# bat_charger.net
KiCad netlist of a schematic drawn in EAGLE
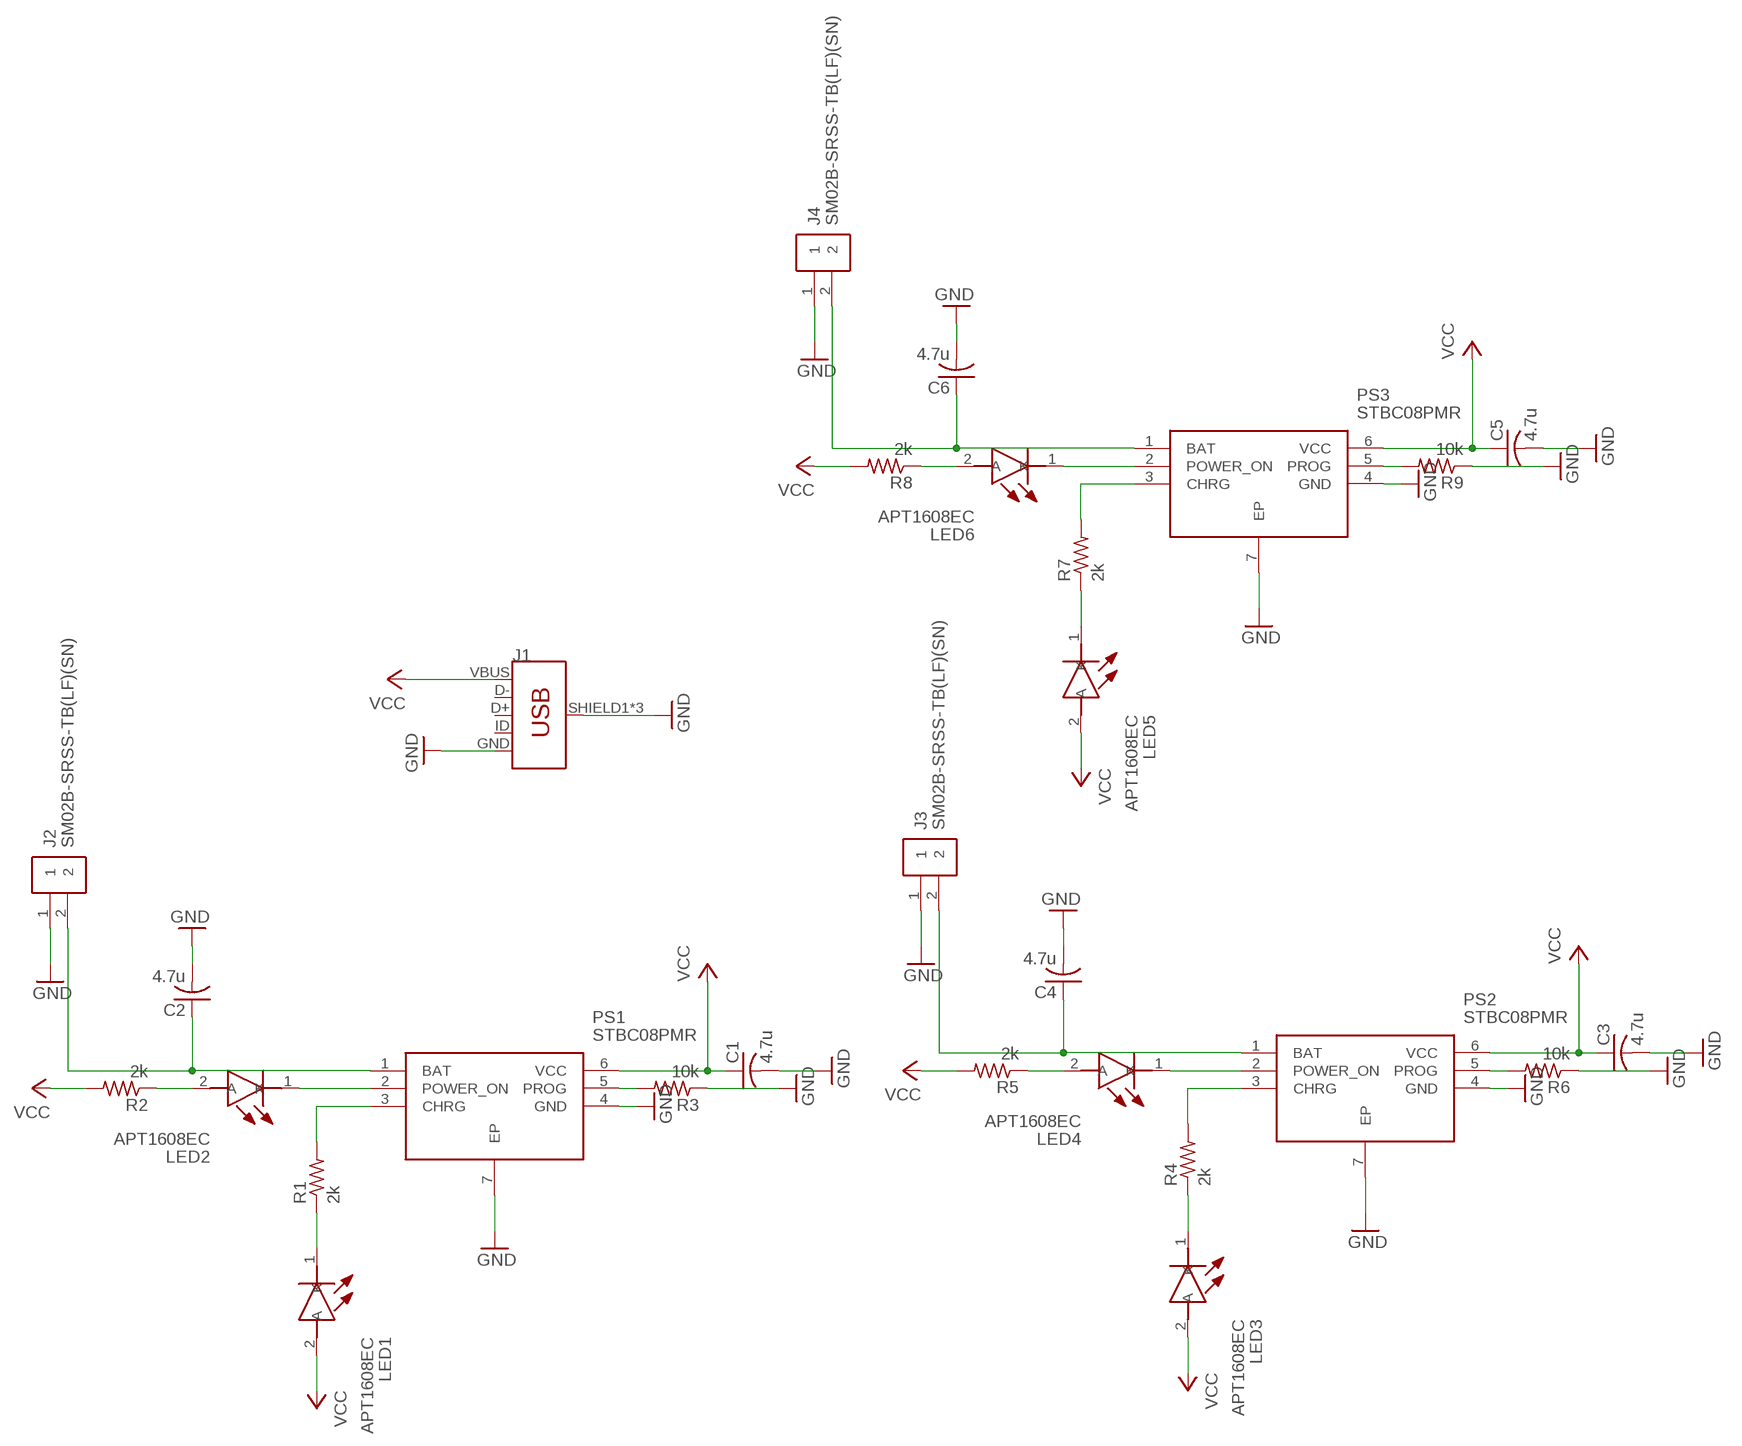
[diagram p0: schematic, sheet 1]

(export (version "E")
  (design (tool "Eeschema 10.0.6"))
  (components
    (comp (ref "C1")
      (value "4.7u")
      (footprint "eagle-import:C0603")
      (libsource (lib "eagle-import") (part "C-USC0603"))
    )
    (comp (ref "C2")
      (value "4.7u")
      (footprint "eagle-import:C0603")
      (libsource (lib "eagle-import") (part "C-USC0603"))
    )
    (comp (ref "C3")
      (value "4.7u")
      (footprint "eagle-import:C0603")
      (libsource (lib "eagle-import") (part "C-USC0603"))
    )
    (comp (ref "C4")
      (value "4.7u")
      (footprint "eagle-import:C0603")
      (libsource (lib "eagle-import") (part "C-USC0603"))
    )
    (comp (ref "C5")
      (value "4.7u")
      (footprint "eagle-import:C0603")
      (libsource (lib "eagle-import") (part "C-USC0603"))
    )
    (comp (ref "C6")
      (value "4.7u")
      (footprint "eagle-import:C0603")
      (libsource (lib "eagle-import") (part "C-USC0603"))
    )
    (comp (ref "J1")
      (value "USB_MICRO-B_FEMALE-SMT")
      (footprint "eagle-import:USB-B-MICRO-SMD")
      (libsource (lib "eagle-import") (part "USB_MICRO-B_FEMALE-SMT"))
    )
    (comp (ref "J2")
      (value "SM02B-SRSS-TB(LF)(SN)")
      (footprint "eagle-import:SM02B-SRSS-TB(LF)(SN)")
      (fields (field (name "MF") "JST Sales"))
      (libsource (lib "eagle-import") (part "SM02B-SRSS-TB(LF)(SN)"))
    )
    (comp (ref "J3")
      (value "SM02B-SRSS-TB(LF)(SN)")
      (footprint "eagle-import:SM02B-SRSS-TB(LF)(SN)")
      (fields (field (name "MF") "JST Sales"))
      (libsource (lib "eagle-import") (part "SM02B-SRSS-TB(LF)(SN)"))
    )
    (comp (ref "J4")
      (value "SM02B-SRSS-TB(LF)(SN)")
      (footprint "eagle-import:SM02B-SRSS-TB(LF)(SN)")
      (fields (field (name "MF") "JST Sales"))
      (libsource (lib "eagle-import") (part "SM02B-SRSS-TB(LF)(SN)"))
    )
    (comp (ref "LED1")
      (value "APT1608EC")
      (footprint "eagle-import:LEDC1608X85N")
      (fields (field (name "MOUSER_PART_NUMBER") "604-APT1608EC"))
      (libsource (lib "eagle-import") (part "APT1608EC"))
    )
    (comp (ref "LED2")
      (value "APT1608EC")
      (footprint "eagle-import:LEDC1608X85N")
      (fields (field (name "MOUSER_PART_NUMBER") "604-APT1608EC"))
      (libsource (lib "eagle-import") (part "APT1608EC"))
    )
    (comp (ref "LED3")
      (value "APT1608EC")
      (footprint "eagle-import:LEDC1608X85N")
      (fields (field (name "MOUSER_PART_NUMBER") "604-APT1608EC"))
      (libsource (lib "eagle-import") (part "APT1608EC"))
    )
    (comp (ref "LED4")
      (value "APT1608EC")
      (footprint "eagle-import:LEDC1608X85N")
      (fields (field (name "MOUSER_PART_NUMBER") "604-APT1608EC"))
      (libsource (lib "eagle-import") (part "APT1608EC"))
    )
    (comp (ref "LED5")
      (value "APT1608EC")
      (footprint "eagle-import:LEDC1608X85N")
      (fields (field (name "MOUSER_PART_NUMBER") "604-APT1608EC"))
      (libsource (lib "eagle-import") (part "APT1608EC"))
    )
    (comp (ref "LED6")
      (value "APT1608EC")
      (footprint "eagle-import:LEDC1608X85N")
      (fields (field (name "MOUSER_PART_NUMBER") "604-APT1608EC"))
      (libsource (lib "eagle-import") (part "APT1608EC"))
    )
    (comp (ref "PS1")
      (value "STBC08PMR")
      (footprint "eagle-import:SON95P300X300X100-7N")
      (fields (field (name "MOUSER_PART_NUMBER") "511-STBC08PMR"))
      (libsource (lib "eagle-import") (part "STBC08PMR"))
    )
    (comp (ref "PS2")
      (value "STBC08PMR")
      (footprint "eagle-import:SON95P300X300X100-7N")
      (fields (field (name "MOUSER_PART_NUMBER") "511-STBC08PMR"))
      (libsource (lib "eagle-import") (part "STBC08PMR"))
    )
    (comp (ref "PS3")
      (value "STBC08PMR")
      (footprint "eagle-import:SON95P300X300X100-7N")
      (fields (field (name "MOUSER_PART_NUMBER") "511-STBC08PMR"))
      (libsource (lib "eagle-import") (part "STBC08PMR"))
    )
    (comp (ref "R1")
      (value "2k")
      (footprint "eagle-import:R0603")
      (libsource (lib "eagle-import") (part "R-US_R0603"))
    )
    (comp (ref "R2")
      (value "2k")
      (footprint "eagle-import:R0603")
      (libsource (lib "eagle-import") (part "R-US_R0603"))
    )
    (comp (ref "R3")
      (value "10k")
      (footprint "eagle-import:R0603")
      (libsource (lib "eagle-import") (part "R-US_R0603"))
    )
    (comp (ref "R4")
      (value "2k")
      (footprint "eagle-import:R0603")
      (libsource (lib "eagle-import") (part "R-US_R0603"))
    )
    (comp (ref "R5")
      (value "2k")
      (footprint "eagle-import:R0603")
      (libsource (lib "eagle-import") (part "R-US_R0603"))
    )
    (comp (ref "R6")
      (value "10k")
      (footprint "eagle-import:R0603")
      (libsource (lib "eagle-import") (part "R-US_R0603"))
    )
    (comp (ref "R7")
      (value "2k")
      (footprint "eagle-import:R0603")
      (libsource (lib "eagle-import") (part "R-US_R0603"))
    )
    (comp (ref "R8")
      (value "2k")
      (footprint "eagle-import:R0603")
      (libsource (lib "eagle-import") (part "R-US_R0603"))
    )
    (comp (ref "R9")
      (value "10k")
      (footprint "eagle-import:R0603")
      (libsource (lib "eagle-import") (part "R-US_R0603"))
    )
  )
  (nets
    (net (code "1") (name "GND") (class "Default")
      (node (ref "C1") (pin "2") (pinfunction "2_2") (pintype "passive"))
      (node (ref "C2") (pin "2") (pinfunction "2_2") (pintype "passive"))
      (node (ref "C3") (pin "2") (pinfunction "2_2") (pintype "passive"))
      (node (ref "C4") (pin "2") (pinfunction "2_2") (pintype "passive"))
      (node (ref "C5") (pin "2") (pinfunction "2_2") (pintype "passive"))
      (node (ref "C6") (pin "2") (pinfunction "2_2") (pintype "passive"))
      (node (ref "J1") (pin "GND") (pinfunction "GND_GND") (pintype "power_in"))
      (node (ref "J1") (pin "SHIELD1") (pinfunction "SHIELD_SHIELD1") (pintype "bidirectional"))
      (node (ref "J1") (pin "SHIELD2") (pinfunction "SHIELD_SHIELD2") (pintype "bidirectional"))
      (node (ref "J1") (pin "SHIELD3") (pinfunction "SHIELD_SHIELD3") (pintype "bidirectional"))
      (node (ref "J2") (pin "1") (pinfunction "1_1") (pintype "bidirectional"))
      (node (ref "J3") (pin "1") (pinfunction "1_1") (pintype "bidirectional"))
      (node (ref "J4") (pin "1") (pinfunction "1_1") (pintype "bidirectional"))
      (node (ref "PS1") (pin "4") (pinfunction "GND_4") (pintype "power_in"))
      (node (ref "PS1") (pin "7") (pinfunction "EP_7") (pintype "power_in"))
      (node (ref "PS2") (pin "4") (pinfunction "GND_4") (pintype "power_in"))
      (node (ref "PS2") (pin "7") (pinfunction "EP_7") (pintype "power_in"))
      (node (ref "PS3") (pin "4") (pinfunction "GND_4") (pintype "power_in"))
      (node (ref "PS3") (pin "7") (pinfunction "EP_7") (pintype "power_in"))
      (node (ref "R3") (pin "1") (pinfunction "1_1") (pintype "passive"))
      (node (ref "R6") (pin "1") (pinfunction "1_1") (pintype "passive"))
      (node (ref "R9") (pin "1") (pinfunction "1_1") (pintype "passive"))
    )
    (net (code "2") (name "Net-(LED1-K)") (class "Default")
      (node (ref "LED1") (pin "1") (pinfunction "K_1") (pintype "bidirectional"))
      (node (ref "R1") (pin "1") (pinfunction "1_1") (pintype "passive"))
    )
    (net (code "3") (name "Net-(LED2-A)") (class "Default")
      (node (ref "LED2") (pin "2") (pinfunction "A_2") (pintype "bidirectional"))
      (node (ref "R2") (pin "1") (pinfunction "1_1") (pintype "passive"))
    )
    (net (code "4") (name "Net-(LED2-K)") (class "Default")
      (node (ref "LED2") (pin "1") (pinfunction "K_1") (pintype "bidirectional"))
      (node (ref "PS1") (pin "2") (pinfunction "POWER_ON_2") (pintype "bidirectional"))
    )
    (net (code "5") (name "Net-(LED3-K)") (class "Default")
      (node (ref "LED3") (pin "1") (pinfunction "K_1") (pintype "bidirectional"))
      (node (ref "R4") (pin "1") (pinfunction "1_1") (pintype "passive"))
    )
    (net (code "6") (name "Net-(LED4-A)") (class "Default")
      (node (ref "LED4") (pin "2") (pinfunction "A_2") (pintype "bidirectional"))
      (node (ref "R5") (pin "1") (pinfunction "1_1") (pintype "passive"))
    )
    (net (code "7") (name "Net-(LED4-K)") (class "Default")
      (node (ref "LED4") (pin "1") (pinfunction "K_1") (pintype "bidirectional"))
      (node (ref "PS2") (pin "2") (pinfunction "POWER_ON_2") (pintype "bidirectional"))
    )
    (net (code "8") (name "Net-(LED5-K)") (class "Default")
      (node (ref "LED5") (pin "1") (pinfunction "K_1") (pintype "bidirectional"))
      (node (ref "R7") (pin "1") (pinfunction "1_1") (pintype "passive"))
    )
    (net (code "9") (name "Net-(LED6-A)") (class "Default")
      (node (ref "LED6") (pin "2") (pinfunction "A_2") (pintype "bidirectional"))
      (node (ref "R8") (pin "1") (pinfunction "1_1") (pintype "passive"))
    )
    (net (code "10") (name "Net-(LED6-K)") (class "Default")
      (node (ref "LED6") (pin "1") (pinfunction "K_1") (pintype "bidirectional"))
      (node (ref "PS3") (pin "2") (pinfunction "POWER_ON_2") (pintype "bidirectional"))
    )
    (net (code "11") (name "Net-(PS1-BAT)") (class "Default")
      (node (ref "C2") (pin "1") (pinfunction "1_1") (pintype "passive"))
      (node (ref "J2") (pin "2") (pinfunction "2_2") (pintype "bidirectional"))
      (node (ref "PS1") (pin "1") (pinfunction "BAT_1") (pintype "output"))
    )
    (net (code "12") (name "Net-(PS1-CHRG)") (class "Default")
      (node (ref "PS1") (pin "3") (pinfunction "CHRG_3") (pintype "output"))
      (node (ref "R1") (pin "2") (pinfunction "2_2") (pintype "passive"))
    )
    (net (code "13") (name "Net-(PS1-PROG)") (class "Default")
      (node (ref "PS1") (pin "5") (pinfunction "PROG_5") (pintype "input"))
      (node (ref "R3") (pin "2") (pinfunction "2_2") (pintype "passive"))
    )
    (net (code "14") (name "Net-(PS2-BAT)") (class "Default")
      (node (ref "C4") (pin "1") (pinfunction "1_1") (pintype "passive"))
      (node (ref "J3") (pin "2") (pinfunction "2_2") (pintype "bidirectional"))
      (node (ref "PS2") (pin "1") (pinfunction "BAT_1") (pintype "output"))
    )
    (net (code "15") (name "Net-(PS2-CHRG)") (class "Default")
      (node (ref "PS2") (pin "3") (pinfunction "CHRG_3") (pintype "output"))
      (node (ref "R4") (pin "2") (pinfunction "2_2") (pintype "passive"))
    )
    (net (code "16") (name "Net-(PS2-PROG)") (class "Default")
      (node (ref "PS2") (pin "5") (pinfunction "PROG_5") (pintype "input"))
      (node (ref "R6") (pin "2") (pinfunction "2_2") (pintype "passive"))
    )
    (net (code "17") (name "Net-(PS3-BAT)") (class "Default")
      (node (ref "C6") (pin "1") (pinfunction "1_1") (pintype "passive"))
      (node (ref "J4") (pin "2") (pinfunction "2_2") (pintype "bidirectional"))
      (node (ref "PS3") (pin "1") (pinfunction "BAT_1") (pintype "output"))
    )
    (net (code "18") (name "Net-(PS3-CHRG)") (class "Default")
      (node (ref "PS3") (pin "3") (pinfunction "CHRG_3") (pintype "output"))
      (node (ref "R7") (pin "2") (pinfunction "2_2") (pintype "passive"))
    )
    (net (code "19") (name "Net-(PS3-PROG)") (class "Default")
      (node (ref "PS3") (pin "5") (pinfunction "PROG_5") (pintype "input"))
      (node (ref "R9") (pin "2") (pinfunction "2_2") (pintype "passive"))
    )
    (net (code "20") (name "VCC") (class "Default")
      (node (ref "C1") (pin "1") (pinfunction "1_1") (pintype "passive"))
      (node (ref "C3") (pin "1") (pinfunction "1_1") (pintype "passive"))
      (node (ref "C5") (pin "1") (pinfunction "1_1") (pintype "passive"))
      (node (ref "J1") (pin "VBUS") (pinfunction "VBUS_VBUS") (pintype "power_in"))
      (node (ref "LED1") (pin "2") (pinfunction "A_2") (pintype "bidirectional"))
      (node (ref "LED3") (pin "2") (pinfunction "A_2") (pintype "bidirectional"))
      (node (ref "LED5") (pin "2") (pinfunction "A_2") (pintype "bidirectional"))
      (node (ref "PS1") (pin "6") (pinfunction "VCC_6") (pintype "power_in"))
      (node (ref "PS2") (pin "6") (pinfunction "VCC_6") (pintype "power_in"))
      (node (ref "PS3") (pin "6") (pinfunction "VCC_6") (pintype "power_in"))
      (node (ref "R2") (pin "2") (pinfunction "2_2") (pintype "passive"))
      (node (ref "R5") (pin "2") (pinfunction "2_2") (pintype "passive"))
      (node (ref "R8") (pin "2") (pinfunction "2_2") (pintype "passive"))
    )
    (net (code "21") (name "unconnected-(J1-PadD+)") (class "Default")
      (node (ref "J1") (pin "D+") (pinfunction "D+_D+") (pintype "bidirectional"))
    )
    (net (code "22") (name "unconnected-(J1-PadD-)") (class "Default")
      (node (ref "J1") (pin "D-") (pinfunction "D-_D-") (pintype "bidirectional"))
    )
    (net (code "23") (name "unconnected-(J1-PadID)") (class "Default")
      (node (ref "J1") (pin "ID") (pinfunction "ID_ID") (pintype "bidirectional"))
    )
  )
)
